# SIM_Socket.net
KiCad netlist of a schematic drawn in Altium Designer
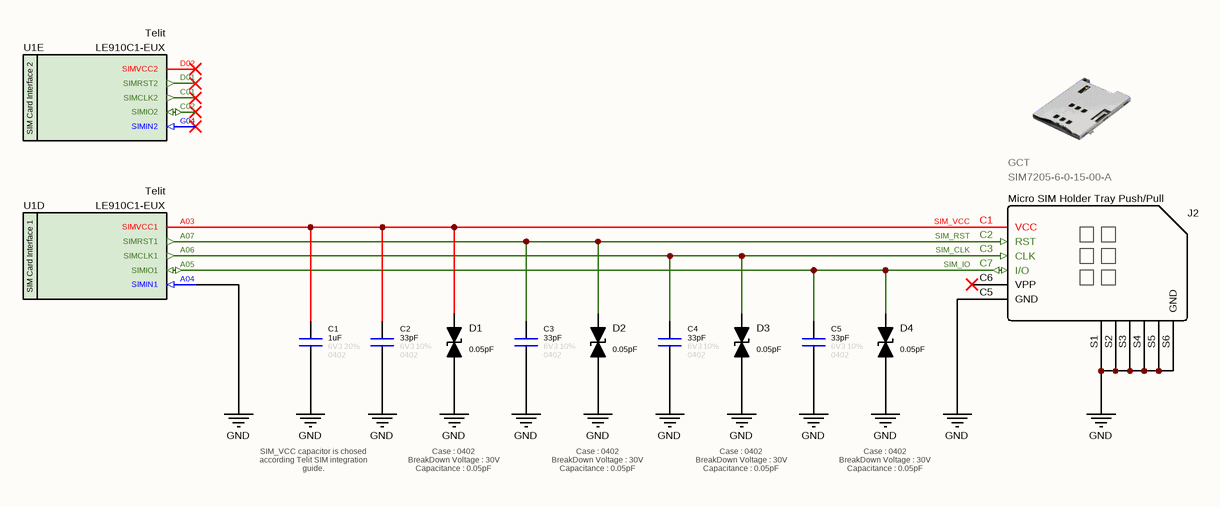
[diagram p0: SIM_Socket.SchDoc]

(export (version "E")
  (design (tool "Eeschema 10.0.6"))
  (components
    (comp (ref "C1")
      (value "1uF")
      (footprint "CAPACITOR_0402")
      (description "Multilayer Ceramic Capacitors - SMD - 6.3V 1uF X5R 0402 20%")
      (fields
        (field (name "MANUFACTURER PART NUMBER") "GRM153R60J105ME95D")
        (field (name "TOLERANCE") "20%")
        (field (name "CASE") "0402")
        (field (name "VOLTAGE") "6V3")
        (field (name "Comment") "Capacitor - 1uF [0402] (Ceramic)")
      )
      (libsource (lib "P101DA_Library") (part "Capacitor - 1uF [0402-6V3]"))
    )
    (comp (ref "C2")
      (value "33pF")
      (footprint "CAPACITOR_0402")
      (description "Capacitor - 33pF [0402] (Ceramic)")
      (fields
        (field (name "MANUFACTURER PART NUMBER") "C0402C330J9RACAUTO")
        (field (name "TOLERANCE") "10%")
        (field (name "CASE") "0402")
        (field (name "VOLTAGE") "6V3")
      )
      (libsource (lib "P101DA_Library") (part "Capacitor - 33pF [0402-6V3]"))
    )
    (comp (ref "C3")
      (value "33pF")
      (footprint "CAPACITOR_0402")
      (description "Capacitor - 33pF [0402] (Ceramic)")
      (fields
        (field (name "MANUFACTURER PART NUMBER") "C0402C330J9RACAUTO")
        (field (name "TOLERANCE") "10%")
        (field (name "CASE") "0402")
        (field (name "VOLTAGE") "6V3")
      )
      (libsource (lib "P101DA_Library") (part "Capacitor - 33pF [0402-6V3]"))
    )
    (comp (ref "C4")
      (value "33pF")
      (footprint "CAPACITOR_0402")
      (description "Capacitor - 33pF [0402] (Ceramic)")
      (fields
        (field (name "MANUFACTURER PART NUMBER") "C0402C330J9RACAUTO")
        (field (name "TOLERANCE") "10%")
        (field (name "CASE") "0402")
        (field (name "VOLTAGE") "6V3")
      )
      (libsource (lib "P101DA_Library") (part "Capacitor - 33pF [0402-6V3]"))
    )
    (comp (ref "C5")
      (value "33pF")
      (footprint "CAPACITOR_0402")
      (description "Capacitor - 33pF [0402] (Ceramic)")
      (fields
        (field (name "MANUFACTURER PART NUMBER") "C0402C330J9RACAUTO")
        (field (name "TOLERANCE") "10%")
        (field (name "CASE") "0402")
        (field (name "VOLTAGE") "6V3")
      )
      (libsource (lib "P101DA_Library") (part "Capacitor - 33pF [0402-6V3]"))
    )
    (comp (ref "D1")
      (value "0402ESDA-MLP1")
      (footprint "INDUCTOR_0402")
      (description "ESD Protection Diodes / TVS Diodes PolySurg 0402 35V .05pF")
      (fields (field (name "CAPACITANCE") "0.05pF"))
      (libsource (lib "Akkoyun") (part "Diode - 0402ESDA-MLP1 (ESD)"))
    )
    (comp (ref "D2")
      (value "0402ESDA-MLP1")
      (footprint "INDUCTOR_0402")
      (description "ESD Protection Diodes / TVS Diodes PolySurg 0402 35V .05pF")
      (fields (field (name "CAPACITANCE") "0.05pF"))
      (libsource (lib "Akkoyun") (part "Diode - 0402ESDA-MLP1 (ESD)"))
    )
    (comp (ref "D3")
      (value "0402ESDA-MLP1")
      (footprint "INDUCTOR_0402")
      (description "ESD Protection Diodes / TVS Diodes PolySurg 0402 35V .05pF")
      (fields (field (name "CAPACITANCE") "0.05pF"))
      (libsource (lib "Akkoyun") (part "Diode - 0402ESDA-MLP1 (ESD)"))
    )
    (comp (ref "D4")
      (value "0402ESDA-MLP1")
      (footprint "INDUCTOR_0402")
      (description "ESD Protection Diodes / TVS Diodes PolySurg 0402 35V .05pF")
      (fields (field (name "CAPACITANCE") "0.05pF"))
      (libsource (lib "Akkoyun") (part "Diode - 0402ESDA-MLP1 (ESD)"))
    )
    (comp (ref "J2")
      (value "SIM7205-6-0-15-00-A")
      (footprint "CONNECTOR - Micro SIM Card")
      (description "Memory Card Connectors Micro SIM Push-Pull, 6P, SMT, 1.48mm Profile, No Peg, Without switch, T&R")
      (fields
        (field (name "CARD TYPE") "Micro SIM Holder Tray Push/Pull")
        (field (name "MANUFACTURER NAME") "GCT")
        (field (name "MANUFACTURER PART NUMBER") "SIM7205-6-0-15-00-A")
      )
      (libsource (lib "Akkoyun") (part "Connector - Sim Holder (Micro SIM)"))
    )
    (comp (ref "U1")
      (value "LE910C1-EUX LTE GSM Module")
      (footprint "LE910 GSM Modem")
      (description "Telit LE910C1-EUX LTE/2G GSM Module")
      (fields
        (field (name "MANUFACTURER PART NUMBER") "LE910C1-EUX")
        (field (name "MANUFACTURER NAME") "Telit")
      )
      (libsource (lib "Akkoyun") (part "IC - LE910C1-EUX"))
    )
  )
  (nets
    (net (code "1") (name "/SIM_CLK") (class "Default")
      (node (ref "C4") (pin "2") (pinfunction "2_2") (pintype "passive"))
      (node (ref "D3") (pin "1") (pinfunction "I/O_1") (pintype "passive"))
      (node (ref "J2") (pin "C3") (pinfunction "CLK_C3") (pintype "input"))
      (node (ref "U1") (pin "A06") (pinfunction "SIMCLK1_A06") (pintype "output"))
    )
    (net (code "2") (name "/SIM_IO") (class "Default")
      (node (ref "C5") (pin "2") (pinfunction "2_2") (pintype "passive"))
      (node (ref "D4") (pin "1") (pinfunction "I/O_1") (pintype "passive"))
      (node (ref "J2") (pin "C7") (pinfunction "I/O_C7") (pintype "bidirectional"))
      (node (ref "U1") (pin "A05") (pinfunction "SIMIO1_A05") (pintype "bidirectional"))
    )
    (net (code "3") (name "/SIM_RST") (class "Default")
      (node (ref "C3") (pin "2") (pinfunction "2_2") (pintype "passive"))
      (node (ref "D2") (pin "1") (pinfunction "I/O_1") (pintype "passive"))
      (node (ref "J2") (pin "C2") (pinfunction "RST_C2") (pintype "input"))
      (node (ref "U1") (pin "A07") (pinfunction "SIMRST1_A07") (pintype "output"))
    )
    (net (code "4") (name "/SIM_VCC") (class "Default")
      (node (ref "C1") (pin "2") (pinfunction "2_2") (pintype "passive"))
      (node (ref "C2") (pin "2") (pinfunction "2_2") (pintype "passive"))
      (node (ref "D1") (pin "1") (pinfunction "I/O_1") (pintype "passive"))
      (node (ref "J2") (pin "C1") (pinfunction "VCC_C1") (pintype "power_in"))
      (node (ref "U1") (pin "A03") (pinfunction "SIMVCC1_A03") (pintype "power_in"))
    )
    (net (code "5") (name "GND") (class "Default")
      (node (ref "C1") (pin "1") (pinfunction "1_1") (pintype "passive"))
      (node (ref "C2") (pin "1") (pinfunction "1_1") (pintype "passive"))
      (node (ref "C3") (pin "1") (pinfunction "1_1") (pintype "passive"))
      (node (ref "C4") (pin "1") (pinfunction "1_1") (pintype "passive"))
      (node (ref "C5") (pin "1") (pinfunction "1_1") (pintype "passive"))
      (node (ref "D1") (pin "2") (pinfunction "GND_2") (pintype "passive"))
      (node (ref "D2") (pin "2") (pinfunction "GND_2") (pintype "passive"))
      (node (ref "D3") (pin "2") (pinfunction "GND_2") (pintype "passive"))
      (node (ref "D4") (pin "2") (pinfunction "GND_2") (pintype "passive"))
      (node (ref "J2") (pin "C5") (pinfunction "GND_C5") (pintype "power_in"))
      (node (ref "J2") (pin "S1") (pinfunction "GND_S1") (pintype "power_in"))
      (node (ref "J2") (pin "S2") (pinfunction "GND_S2") (pintype "power_in"))
      (node (ref "J2") (pin "S3") (pinfunction "GND_S3") (pintype "power_in"))
      (node (ref "J2") (pin "S4") (pinfunction "GND_S4") (pintype "power_in"))
      (node (ref "J2") (pin "S5") (pinfunction "GND_S5") (pintype "power_in"))
      (node (ref "J2") (pin "S6") (pinfunction "GND_S6") (pintype "power_in"))
      (node (ref "U1") (pin "A04") (pinfunction "SIMIN1_A04") (pintype "input"))
    )
    (net (code "6") (name "unconnected-(J2-VPP-PadC6)") (class "Default")
      (node (ref "J2") (pin "C6") (pinfunction "VPP_C6") (pintype "power_in+no_connect"))
    )
    (net (code "7") (name "unconnected-(U1E-SIMCLK2-PadC01)") (class "Default")
      (node (ref "U1") (pin "C01") (pinfunction "SIMCLK2_C01") (pintype "output+no_connect"))
    )
    (net (code "8") (name "unconnected-(U1E-SIMIN2-PadG04)") (class "Default")
      (node (ref "U1") (pin "G04") (pinfunction "SIMIN2_G04") (pintype "input+no_connect"))
    )
    (net (code "9") (name "unconnected-(U1E-SIMIO2-PadC02)") (class "Default")
      (node (ref "U1") (pin "C02") (pinfunction "SIMIO2_C02") (pintype "bidirectional+no_connect"))
    )
    (net (code "10") (name "unconnected-(U1E-SIMRST2-PadD01)") (class "Default")
      (node (ref "U1") (pin "D01") (pinfunction "SIMRST2_D01") (pintype "output+no_connect"))
    )
    (net (code "11") (name "unconnected-(U1E-SIMVCC2-PadD02)") (class "Default")
      (node (ref "U1") (pin "D02") (pinfunction "SIMVCC2_D02") (pintype "passive+no_connect"))
    )
  )
)
